# hand_foot_forearm_leg_LED.net
KiCad netlist of a schematic drawn in EAGLE
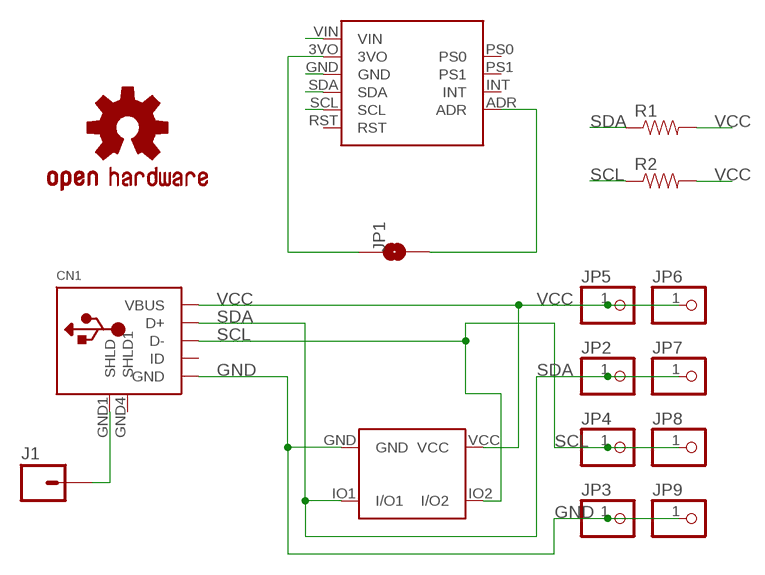
[diagram p0: schematic, sheet 1]

(export (version "E")
  (design (tool "Eeschema 10.0.6"))
  (components
    (comp (ref "CN1")
      (value "USB")
      (footprint "eagle-import:USB-MINIB-THM-MOLEX_NOSLK")
      (libsource (lib "eagle-import") (part "USB"))
    )
    (comp (ref "J1")
      (value "M01PTH")
      (footprint "eagle-import:1X01")
      (libsource (lib "eagle-import") (part "M01PTH"))
    )
    (comp (ref "JP1")
      (value "JUMPER-PAD-2-NO")
      (footprint "eagle-import:PAD-JUMPER-2-NO_NO_SILK")
      (libsource (lib "eagle-import") (part "JUMPER-PAD-2-NO"))
    )
    (comp (ref "JP2")
      (value "PINHD-1X1CB")
      (footprint "eagle-import:1X01-CLEANBIG")
      (libsource (lib "eagle-import") (part "PINHD-1X1CB"))
    )
    (comp (ref "JP3")
      (value "PINHD-1X1CB")
      (footprint "eagle-import:1X01-CLEANBIG")
      (libsource (lib "eagle-import") (part "PINHD-1X1CB"))
    )
    (comp (ref "JP4")
      (value "PINHD-1X1CB")
      (footprint "eagle-import:1X01-CLEANBIG")
      (libsource (lib "eagle-import") (part "PINHD-1X1CB"))
    )
    (comp (ref "JP5")
      (value "PINHD-1X1CB")
      (footprint "eagle-import:1X01-CLEANBIG")
      (libsource (lib "eagle-import") (part "PINHD-1X1CB"))
    )
    (comp (ref "JP6")
      (value "PINHD-1X1CB")
      (footprint "eagle-import:1X01-CLEANBIG")
      (libsource (lib "eagle-import") (part "PINHD-1X1CB"))
    )
    (comp (ref "JP7")
      (value "PINHD-1X1CB")
      (footprint "eagle-import:1X01-CLEANBIG")
      (libsource (lib "eagle-import") (part "PINHD-1X1CB"))
    )
    (comp (ref "JP8")
      (value "PINHD-1X1CB")
      (footprint "eagle-import:1X01-CLEANBIG")
      (libsource (lib "eagle-import") (part "PINHD-1X1CB"))
    )
    (comp (ref "JP9")
      (value "PINHD-1X1CB")
      (footprint "eagle-import:1X01-CLEANBIG")
      (libsource (lib "eagle-import") (part "PINHD-1X1CB"))
    )
    (comp (ref "LOGO1")
      (value "OSHW-LOGOS")
      (footprint "eagle-import:OSHW-LOGO-S")
      (libsource (lib "eagle-import") (part "OSHW-LOGOS"))
    )
    (comp (ref "R1")
      (value "RESISTORAXIAL-0.3")
      (footprint "eagle-import:AXIAL-0.3")
      (libsource (lib "eagle-import") (part "RESISTORAXIAL-0.3"))
    )
    (comp (ref "R2")
      (value "RESISTORAXIAL-0.3")
      (footprint "eagle-import:AXIAL-0.3")
      (libsource (lib "eagle-import") (part "RESISTORAXIAL-0.3"))
    )
    (comp (ref "U$1")
      (value "BNO_055_BKOUT")
      (footprint "eagle-import:BNO_BKOUT")
      (libsource (lib "eagle-import") (part "BNO_055_BKOUT"))
    )
    (comp (ref "U$2")
      (value "TVS_ARRAY_CD143A")
      (footprint "eagle-import:SOT-143")
      (libsource (lib "eagle-import") (part "TVS_ARRAY_CD143A"))
    )
  )
  (nets
    (net (code "1") (name "/GND") (class "Default")
      (node (ref "CN1") (pin "GND") (pinfunction "GND_GND") (pintype "power_in"))
      (node (ref "JP3") (pin "1") (pinfunction "1_1") (pintype "passive"))
      (node (ref "JP9") (pin "1") (pinfunction "1_1") (pintype "passive"))
      (node (ref "U$1") (pin "GND") (pinfunction "GND_GND") (pintype "bidirectional"))
      (node (ref "U$2") (pin "GND") (pinfunction "GND_GND") (pintype "power_in"))
    )
    (net (code "2") (name "/SCL") (class "Default")
      (node (ref "CN1") (pin "D-") (pinfunction "D-_D-") (pintype "bidirectional"))
      (node (ref "JP4") (pin "1") (pinfunction "1_1") (pintype "passive"))
      (node (ref "JP8") (pin "1") (pinfunction "1_1") (pintype "passive"))
      (node (ref "R2") (pin "P$1") (pinfunction "1_P$1") (pintype "passive"))
      (node (ref "U$1") (pin "SCL") (pinfunction "SCL_SCL") (pintype "bidirectional"))
      (node (ref "U$2") (pin "IO2") (pinfunction "I/O2_IO2") (pintype "bidirectional"))
    )
    (net (code "3") (name "/SDA") (class "Default")
      (node (ref "CN1") (pin "D+") (pinfunction "D+_D+") (pintype "bidirectional"))
      (node (ref "JP2") (pin "1") (pinfunction "1_1") (pintype "passive"))
      (node (ref "JP7") (pin "1") (pinfunction "1_1") (pintype "passive"))
      (node (ref "R1") (pin "P$1") (pinfunction "1_P$1") (pintype "passive"))
      (node (ref "U$1") (pin "SDA") (pinfunction "SDA_SDA") (pintype "bidirectional"))
      (node (ref "U$2") (pin "IO1") (pinfunction "I/O1_IO1") (pintype "bidirectional"))
    )
    (net (code "4") (name "/VCC") (class "Default")
      (node (ref "CN1") (pin "VBUS") (pinfunction "VBUS_VBUS") (pintype "power_in"))
      (node (ref "JP5") (pin "1") (pinfunction "1_1") (pintype "passive"))
      (node (ref "JP6") (pin "1") (pinfunction "1_1") (pintype "passive"))
      (node (ref "R1") (pin "P$2") (pinfunction "2_P$2") (pintype "passive"))
      (node (ref "R2") (pin "P$2") (pinfunction "2_P$2") (pintype "passive"))
      (node (ref "U$1") (pin "VIN") (pinfunction "VIN_VIN") (pintype "bidirectional"))
      (node (ref "U$2") (pin "VCC") (pinfunction "VCC_VCC") (pintype "power_in"))
    )
    (net (code "5") (name "Net-(CN1-SHLD)") (class "Default")
      (node (ref "CN1") (pin "GND1") (pinfunction "SHLD_GND1") (pintype "bidirectional"))
      (node (ref "J1") (pin "1") (pinfunction "1_1") (pintype "passive"))
    )
    (net (code "6") (name "Net-(JP1-Pad1)") (class "Default")
      (node (ref "JP1") (pin "1") (pinfunction "1_1") (pintype "passive"))
      (node (ref "U$1") (pin "3VO") (pinfunction "3VO_3VO") (pintype "bidirectional"))
    )
    (net (code "7") (name "Net-(JP1-Pad2)") (class "Default")
      (node (ref "JP1") (pin "2") (pinfunction "2_2") (pintype "passive"))
      (node (ref "U$1") (pin "ADR") (pinfunction "ADR_ADR") (pintype "bidirectional"))
    )
    (net (code "8") (name "unconnected-(CN1-PadID)") (class "Default")
      (node (ref "CN1") (pin "ID") (pinfunction "ID_ID") (pintype "bidirectional"))
    )
    (net (code "9") (name "unconnected-(CN1-SHLD1-PadGND4)") (class "Default")
      (node (ref "CN1") (pin "GND4") (pinfunction "SHLD1_GND4") (pintype "bidirectional"))
    )
    (net (code "10") (name "unconnected-(U$1-PadINT)") (class "Default")
      (node (ref "U$1") (pin "INT") (pinfunction "INT_INT") (pintype "bidirectional"))
    )
    (net (code "11") (name "unconnected-(U$1-PadPS0)") (class "Default")
      (node (ref "U$1") (pin "PS0") (pinfunction "PS0_PS0") (pintype "bidirectional"))
    )
    (net (code "12") (name "unconnected-(U$1-PadPS1)") (class "Default")
      (node (ref "U$1") (pin "PS1") (pinfunction "PS1_PS1") (pintype "bidirectional"))
    )
    (net (code "13") (name "unconnected-(U$1-PadRST)") (class "Default")
      (node (ref "U$1") (pin "RST") (pinfunction "RST_RST") (pintype "bidirectional"))
    )
  )
)
